# hdmi_trigger_interface.net
KiCad netlist of a schematic drawn in EAGLE
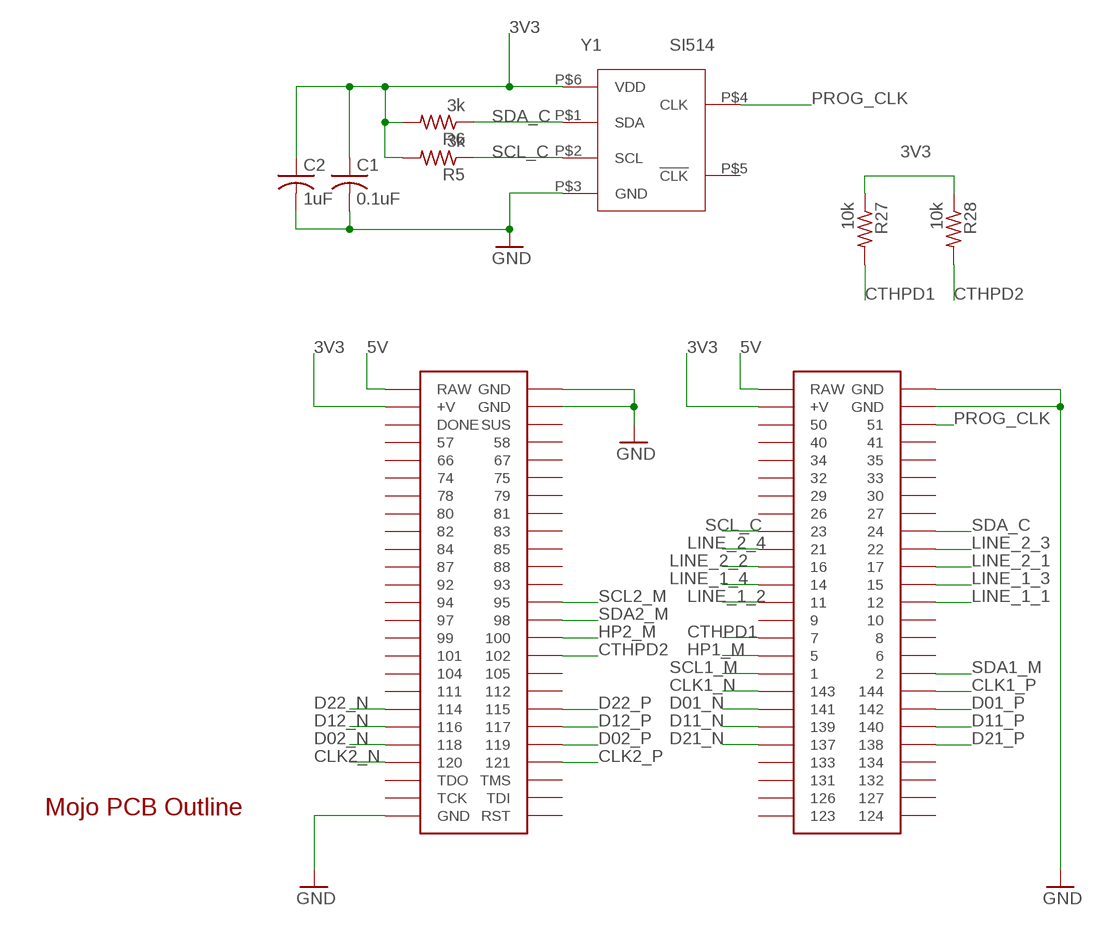
[diagram p0: schematic, sheet 1]
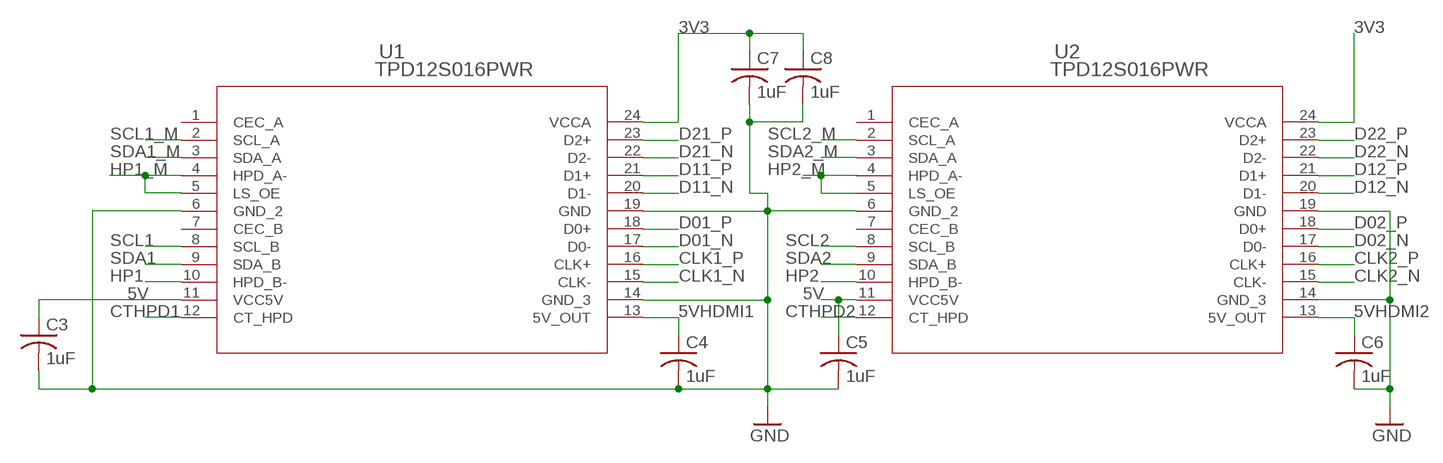
[diagram p1: schematic, sheet 2]
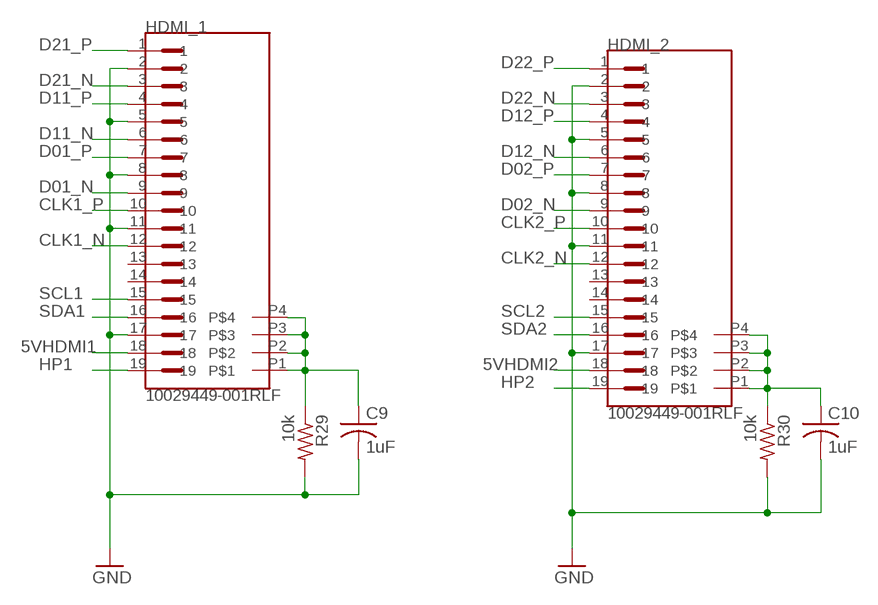
[diagram p2: schematic, sheet 3]
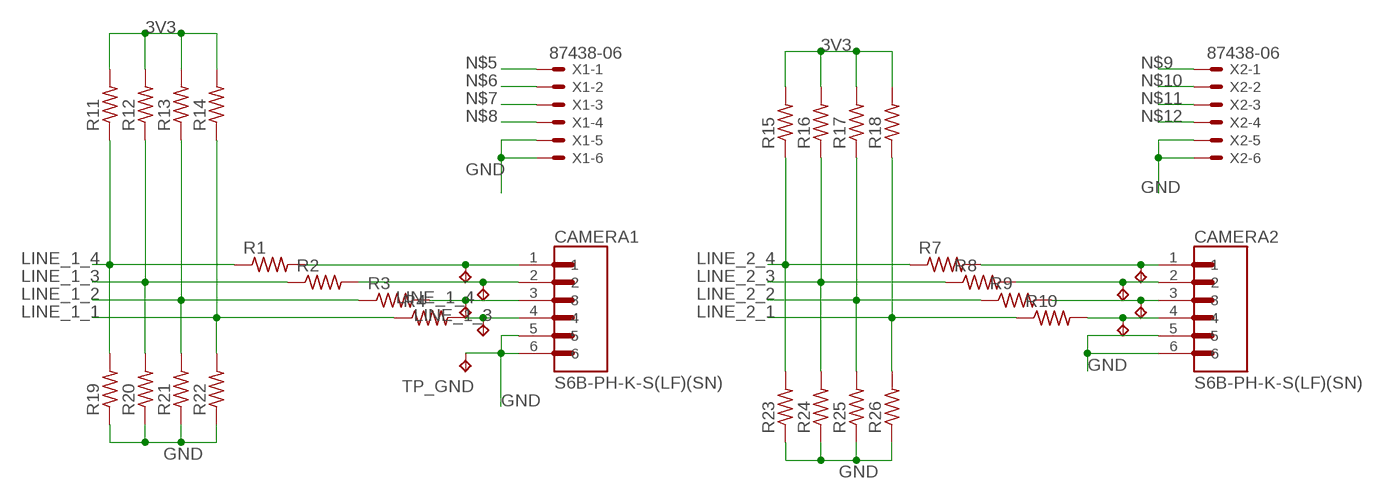
[diagram p3: schematic, sheet 4]

(export (version "E")
  (design (tool "Eeschema 10.0.6"))
  (components
    (comp (ref "C3")
      (value "1uF")
      (footprint "eagle-import:C0603")
      (libsource (lib "eagle-import") (part "C-USC0603"))
    )
    (comp (ref "C4")
      (value "1uF")
      (footprint "eagle-import:C0603")
      (libsource (lib "eagle-import") (part "C-USC0603"))
    )
    (comp (ref "C5")
      (value "1uF")
      (footprint "eagle-import:C0603")
      (libsource (lib "eagle-import") (part "C-USC0603"))
    )
    (comp (ref "C6")
      (value "1uF")
      (footprint "eagle-import:C0603")
      (libsource (lib "eagle-import") (part "C-USC0603"))
    )
    (comp (ref "C7")
      (value "1uF")
      (footprint "eagle-import:C0603")
      (libsource (lib "eagle-import") (part "C-USC0603"))
    )
    (comp (ref "C8")
      (value "1uF")
      (footprint "eagle-import:C0603")
      (libsource (lib "eagle-import") (part "C-USC0603"))
    )
    (comp (ref "U1")
      (value "TPD12S016PWR")
      (footprint "eagle-import:PW24")
      (libsource (lib "eagle-import") (part "TPD12S016PWR"))
    )
    (comp (ref "U2")
      (value "TPD12S016PWR")
      (footprint "eagle-import:PW24")
      (libsource (lib "eagle-import") (part "TPD12S016PWR"))
    )
    (comp (ref "C9")
      (value "1uF")
      (footprint "eagle-import:C0603")
      (libsource (lib "eagle-import") (part "C-USC0603"))
    )
    (comp (ref "C10")
      (value "1uF")
      (footprint "eagle-import:C0603")
      (libsource (lib "eagle-import") (part "C-USC0603"))
    )
    (comp (ref "HDMI_1")
      (value "10029449-001RLF")
      (footprint "eagle-import:FCI_10029449-001RLF")
      (fields (field (name "MF") "Amphenol FCI"))
      (libsource (lib "eagle-import") (part "10029449-001RLF"))
    )
    (comp (ref "HDMI_2")
      (value "10029449-001RLF")
      (footprint "eagle-import:FCI_10029449-001RLF")
      (fields (field (name "MF") "Amphenol FCI"))
      (libsource (lib "eagle-import") (part "10029449-001RLF"))
    )
    (comp (ref "R29")
      (value "10k")
      (footprint "eagle-import:R0603")
      (libsource (lib "eagle-import") (part "R-US_R0603"))
    )
    (comp (ref "R30")
      (value "10k")
      (footprint "eagle-import:R0603")
      (libsource (lib "eagle-import") (part "R-US_R0603"))
    )
    (comp (ref "CAMERA1")
      (value "S6B-PH-K-S(LF)(SN)")
      (footprint "eagle-import:JST_S6B-PH-K-S(LF)(SN)")
      (fields
        (field (name "DIGI-KEY_PART_NUMBER") "455-1723-ND")
        (field (name "MF") "JST Sales")
        (field (name "MP") "S6B-PH-K-S_LF__SN_")
      )
      (libsource (lib "eagle-import") (part "S6B-PH-K-S(LF)(SN)"))
    )
    (comp (ref "CAMERA2")
      (value "S6B-PH-K-S(LF)(SN)")
      (footprint "eagle-import:JST_S6B-PH-K-S(LF)(SN)")
      (fields
        (field (name "DIGI-KEY_PART_NUMBER") "455-1723-ND")
        (field (name "MF") "JST Sales")
        (field (name "MP") "S6B-PH-K-S_LF__SN_")
      )
      (libsource (lib "eagle-import") (part "S6B-PH-K-S(LF)(SN)"))
    )
    (comp (ref "LINE_1_1")
      (value "TPTP16R")
      (footprint "eagle-import:TP16R")
      (libsource (lib "eagle-import") (part "TPTP16R"))
    )
    (comp (ref "LINE_1_2")
      (value "TPTP16R")
      (footprint "eagle-import:TP16R")
      (libsource (lib "eagle-import") (part "TPTP16R"))
    )
    (comp (ref "LINE_1_3")
      (value "TPTP16R")
      (footprint "eagle-import:TP16R")
      (libsource (lib "eagle-import") (part "TPTP16R"))
    )
    (comp (ref "LINE_1_4")
      (value "TPTP16R")
      (footprint "eagle-import:TP16R")
      (libsource (lib "eagle-import") (part "TPTP16R"))
    )
    (comp (ref "LINE_2_1")
      (value "LINE_1")
      (footprint "eagle-import:TP16R")
      (libsource (lib "eagle-import") (part "TPTP16R"))
    )
    (comp (ref "LINE_2_2")
      (value "LINE_2")
      (footprint "eagle-import:TP16R")
      (libsource (lib "eagle-import") (part "TPTP16R"))
    )
    (comp (ref "LINE_2_3")
      (value "LINE_3")
      (footprint "eagle-import:TP16R")
      (libsource (lib "eagle-import") (part "TPTP16R"))
    )
    (comp (ref "LINE_4")
      (value "LINE_1")
      (footprint "eagle-import:TP16R")
      (libsource (lib "eagle-import") (part "TPTP16R"))
    )
    (comp (ref "R1")
      (value "R-US_R0603")
      (footprint "eagle-import:R0603")
      (libsource (lib "eagle-import") (part "R-US_R0603"))
    )
    (comp (ref "R2")
      (value "R-US_R0603")
      (footprint "eagle-import:R0603")
      (libsource (lib "eagle-import") (part "R-US_R0603"))
    )
    (comp (ref "R3")
      (value "R-US_R0603")
      (footprint "eagle-import:R0603")
      (libsource (lib "eagle-import") (part "R-US_R0603"))
    )
    (comp (ref "R4")
      (value "R-US_R0603")
      (footprint "eagle-import:R0603")
      (libsource (lib "eagle-import") (part "R-US_R0603"))
    )
    (comp (ref "R7")
      (value "R-US_R0603")
      (footprint "eagle-import:R0603")
      (libsource (lib "eagle-import") (part "R-US_R0603"))
    )
    (comp (ref "R8")
      (value "R-US_R0603")
      (footprint "eagle-import:R0603")
      (libsource (lib "eagle-import") (part "R-US_R0603"))
    )
    (comp (ref "R9")
      (value "R-US_R0603")
      (footprint "eagle-import:R0603")
      (libsource (lib "eagle-import") (part "R-US_R0603"))
    )
    (comp (ref "R10")
      (value "R-US_R0603")
      (footprint "eagle-import:R0603")
      (libsource (lib "eagle-import") (part "R-US_R0603"))
    )
    (comp (ref "R11")
      (value "R-US_R0603")
      (footprint "eagle-import:R0603")
      (libsource (lib "eagle-import") (part "R-US_R0603"))
    )
    (comp (ref "R12")
      (value "R-US_R0603")
      (footprint "eagle-import:R0603")
      (libsource (lib "eagle-import") (part "R-US_R0603"))
    )
    (comp (ref "R13")
      (value "R-US_R0603")
      (footprint "eagle-import:R0603")
      (libsource (lib "eagle-import") (part "R-US_R0603"))
    )
    (comp (ref "R14")
      (value "R-US_R0603")
      (footprint "eagle-import:R0603")
      (libsource (lib "eagle-import") (part "R-US_R0603"))
    )
    (comp (ref "R15")
      (value "R-US_R0603")
      (footprint "eagle-import:R0603")
      (libsource (lib "eagle-import") (part "R-US_R0603"))
    )
    (comp (ref "R16")
      (value "R-US_R0603")
      (footprint "eagle-import:R0603")
      (libsource (lib "eagle-import") (part "R-US_R0603"))
    )
    (comp (ref "R17")
      (value "R-US_R0603")
      (footprint "eagle-import:R0603")
      (libsource (lib "eagle-import") (part "R-US_R0603"))
    )
    (comp (ref "R18")
      (value "R-US_R0603")
      (footprint "eagle-import:R0603")
      (libsource (lib "eagle-import") (part "R-US_R0603"))
    )
    (comp (ref "R19")
      (value "R-US_R0603")
      (footprint "eagle-import:R0603")
      (libsource (lib "eagle-import") (part "R-US_R0603"))
    )
    (comp (ref "R20")
      (value "R-US_R0603")
      (footprint "eagle-import:R0603")
      (libsource (lib "eagle-import") (part "R-US_R0603"))
    )
    (comp (ref "R21")
      (value "R-US_R0603")
      (footprint "eagle-import:R0603")
      (libsource (lib "eagle-import") (part "R-US_R0603"))
    )
    (comp (ref "R22")
      (value "R-US_R0603")
      (footprint "eagle-import:R0603")
      (libsource (lib "eagle-import") (part "R-US_R0603"))
    )
    (comp (ref "R23")
      (value "R-US_R0603")
      (footprint "eagle-import:R0603")
      (libsource (lib "eagle-import") (part "R-US_R0603"))
    )
    (comp (ref "R24")
      (value "R-US_R0603")
      (footprint "eagle-import:R0603")
      (libsource (lib "eagle-import") (part "R-US_R0603"))
    )
    (comp (ref "R25")
      (value "R-US_R0603")
      (footprint "eagle-import:R0603")
      (libsource (lib "eagle-import") (part "R-US_R0603"))
    )
    (comp (ref "R26")
      (value "R-US_R0603")
      (footprint "eagle-import:R0603")
      (libsource (lib "eagle-import") (part "R-US_R0603"))
    )
    (comp (ref "TP_GND")
      (value "TPTP16R")
      (footprint "eagle-import:TP16R")
      (libsource (lib "eagle-import") (part "TPTP16R"))
    )
    (comp (ref "X1")
      (value "87438-06")
      (footprint "eagle-import:87438-06")
      (fields (field (name "MF") "MOLEX") (field (name "MPN") "87438-0643"))
      (libsource (lib "eagle-import") (part "87438-06"))
    )
    (comp (ref "X2")
      (value "87438-06")
      (footprint "eagle-import:87438-06")
      (fields (field (name "MF") "MOLEX") (field (name "MPN") "87438-0643"))
      (libsource (lib "eagle-import") (part "87438-06"))
    )
    (comp (ref "C1")
      (value "0.1uF")
      (footprint "eagle-import:C0603")
      (libsource (lib "eagle-import") (part "C-USC0603"))
    )
    (comp (ref "C2")
      (value "1uF")
      (footprint "eagle-import:C0603")
      (libsource (lib "eagle-import") (part "C-USC0603"))
    )
    (comp (ref "R5")
      (value "3k")
      (footprint "eagle-import:R0603")
      (libsource (lib "eagle-import") (part "R-US_R0603"))
    )
    (comp (ref "R6")
      (value "3k")
      (footprint "eagle-import:R0603")
      (libsource (lib "eagle-import") (part "R-US_R0603"))
    )
    (comp (ref "R27")
      (value "10k")
      (footprint "eagle-import:R0603")
      (libsource (lib "eagle-import") (part "R-US_R0603"))
    )
    (comp (ref "R28")
      (value "10k")
      (footprint "eagle-import:R0603")
      (libsource (lib "eagle-import") (part "R-US_R0603"))
    )
    (comp (ref "U$1")
      (value "MOJOV3")
      (footprint "eagle-import:MOJO_V3")
      (libsource (lib "eagle-import") (part "MOJOV3"))
    )
    (comp (ref "U$2")
      (value "MOJO_OUTLINE")
      (footprint "eagle-import:MOJO_OUTLINE")
      (libsource (lib "eagle-import") (part "MOJO_OUTLINE"))
    )
    (comp (ref "Y1")
      (value "SI514")
      (footprint "eagle-import:XTAL-6PIN")
      (libsource (lib "eagle-import") (part "SI514"))
    )
  )
  (nets
    (net (code "1") (name "3V3") (class "Default")
      (node (ref "C1") (pin "1") (pinfunction "1_1") (pintype "passive"))
      (node (ref "C2") (pin "1") (pinfunction "1_1") (pintype "passive"))
      (node (ref "C7") (pin "1") (pinfunction "1_1") (pintype "passive"))
      (node (ref "C8") (pin "1") (pinfunction "1_1") (pintype "passive"))
      (node (ref "R11") (pin "2") (pinfunction "2_2") (pintype "passive"))
      (node (ref "R12") (pin "2") (pinfunction "2_2") (pintype "passive"))
      (node (ref "R13") (pin "2") (pinfunction "2_2") (pintype "passive"))
      (node (ref "R14") (pin "2") (pinfunction "2_2") (pintype "passive"))
      (node (ref "R15") (pin "2") (pinfunction "2_2") (pintype "passive"))
      (node (ref "R16") (pin "2") (pinfunction "2_2") (pintype "passive"))
      (node (ref "R17") (pin "2") (pinfunction "2_2") (pintype "passive"))
      (node (ref "R18") (pin "2") (pinfunction "2_2") (pintype "passive"))
      (node (ref "R27") (pin "1") (pinfunction "1_1") (pintype "passive"))
      (node (ref "R28") (pin "1") (pinfunction "1_1") (pintype "passive"))
      (node (ref "R5") (pin "2") (pinfunction "2_2") (pintype "passive"))
      (node (ref "R6") (pin "2") (pinfunction "2_2") (pintype "passive"))
      (node (ref "U$1") (pin "V@1") (pinfunction "+V_V@1") (pintype "power_in"))
      (node (ref "U$1") (pin "V@2") (pinfunction "+V_V@2") (pintype "power_in"))
      (node (ref "U1") (pin "24") (pinfunction "VCCA_24") (pintype "power_in"))
      (node (ref "U2") (pin "24") (pinfunction "VCCA_24") (pintype "power_in"))
      (node (ref "Y1") (pin "P$6") (pinfunction "VDD_P$6") (pintype "bidirectional"))
    )
    (net (code "2") (name "5V") (class "Default")
      (node (ref "C3") (pin "1") (pinfunction "1_1") (pintype "passive"))
      (node (ref "C5") (pin "1") (pinfunction "1_1") (pintype "passive"))
      (node (ref "U$1") (pin "RAW@1") (pinfunction "RAW_RAW@1") (pintype "power_in"))
      (node (ref "U$1") (pin "RAW@2") (pinfunction "RAW_RAW@2") (pintype "power_in"))
      (node (ref "U1") (pin "11") (pinfunction "VCC5V_11") (pintype "power_in"))
      (node (ref "U2") (pin "11") (pinfunction "VCC5V_11") (pintype "power_in"))
    )
    (net (code "3") (name "5VHDMI1") (class "Default")
      (node (ref "C4") (pin "1") (pinfunction "1_1") (pintype "passive"))
      (node (ref "HDMI_1") (pin "18") (pinfunction "18_18") (pintype "passive"))
      (node (ref "U1") (pin "13") (pinfunction "5V_OUT_13") (pintype "output"))
    )
    (net (code "4") (name "5VHDMI2") (class "Default")
      (node (ref "C6") (pin "1") (pinfunction "1_1") (pintype "passive"))
      (node (ref "HDMI_2") (pin "18") (pinfunction "18_18") (pintype "passive"))
      (node (ref "U2") (pin "13") (pinfunction "5V_OUT_13") (pintype "output"))
    )
    (net (code "5") (name "CLK1_N") (class "Default")
      (node (ref "HDMI_1") (pin "12") (pinfunction "12_12") (pintype "passive"))
      (node (ref "U$1") (pin "143") (pinfunction "143_143") (pintype "bidirectional"))
      (node (ref "U1") (pin "15") (pinfunction "CLK-_15") (pintype "passive"))
    )
    (net (code "6") (name "CLK1_P") (class "Default")
      (node (ref "HDMI_1") (pin "10") (pinfunction "10_10") (pintype "passive"))
      (node (ref "U$1") (pin "144") (pinfunction "144_144") (pintype "bidirectional"))
      (node (ref "U1") (pin "16") (pinfunction "CLK+_16") (pintype "passive"))
    )
    (net (code "7") (name "CLK2_N") (class "Default")
      (node (ref "HDMI_2") (pin "12") (pinfunction "12_12") (pintype "passive"))
      (node (ref "U$1") (pin "120") (pinfunction "120_120") (pintype "bidirectional"))
      (node (ref "U2") (pin "15") (pinfunction "CLK-_15") (pintype "passive"))
    )
    (net (code "8") (name "CLK2_P") (class "Default")
      (node (ref "HDMI_2") (pin "10") (pinfunction "10_10") (pintype "passive"))
      (node (ref "U$1") (pin "121") (pinfunction "121_121") (pintype "bidirectional"))
      (node (ref "U2") (pin "16") (pinfunction "CLK+_16") (pintype "passive"))
    )
    (net (code "9") (name "CTHPD1") (class "Default")
      (node (ref "R27") (pin "2") (pinfunction "2_2") (pintype "passive"))
      (node (ref "U$1") (pin "7") (pinfunction "7_7") (pintype "bidirectional"))
      (node (ref "U1") (pin "12") (pinfunction "CT_HPD_12") (pintype "input"))
    )
    (net (code "10") (name "CTHPD2") (class "Default")
      (node (ref "R28") (pin "2") (pinfunction "2_2") (pintype "passive"))
      (node (ref "U$1") (pin "102") (pinfunction "102_102") (pintype "bidirectional"))
      (node (ref "U2") (pin "12") (pinfunction "CT_HPD_12") (pintype "input"))
    )
    (net (code "11") (name "D01_N") (class "Default")
      (node (ref "HDMI_1") (pin "9") (pinfunction "9_9") (pintype "passive"))
      (node (ref "U$1") (pin "141") (pinfunction "141_141") (pintype "bidirectional"))
      (node (ref "U1") (pin "17") (pinfunction "D0-_17") (pintype "passive"))
    )
    (net (code "12") (name "D01_P") (class "Default")
      (node (ref "HDMI_1") (pin "7") (pinfunction "7_7") (pintype "passive"))
      (node (ref "U$1") (pin "142") (pinfunction "142_142") (pintype "bidirectional"))
      (node (ref "U1") (pin "18") (pinfunction "D0+_18") (pintype "passive"))
    )
    (net (code "13") (name "D02_N") (class "Default")
      (node (ref "HDMI_2") (pin "9") (pinfunction "9_9") (pintype "passive"))
      (node (ref "U$1") (pin "118") (pinfunction "118_118") (pintype "bidirectional"))
      (node (ref "U2") (pin "17") (pinfunction "D0-_17") (pintype "passive"))
    )
    (net (code "14") (name "D02_P") (class "Default")
      (node (ref "HDMI_2") (pin "7") (pinfunction "7_7") (pintype "passive"))
      (node (ref "U$1") (pin "119") (pinfunction "119_119") (pintype "bidirectional"))
      (node (ref "U2") (pin "18") (pinfunction "D0+_18") (pintype "passive"))
    )
    (net (code "15") (name "D11_N") (class "Default")
      (node (ref "HDMI_1") (pin "6") (pinfunction "6_6") (pintype "passive"))
      (node (ref "U$1") (pin "139") (pinfunction "139_139") (pintype "bidirectional"))
      (node (ref "U1") (pin "20") (pinfunction "D1-_20") (pintype "passive"))
    )
    (net (code "16") (name "D11_P") (class "Default")
      (node (ref "HDMI_1") (pin "4") (pinfunction "4_4") (pintype "passive"))
      (node (ref "U$1") (pin "140") (pinfunction "140_140") (pintype "bidirectional"))
      (node (ref "U1") (pin "21") (pinfunction "D1+_21") (pintype "passive"))
    )
    (net (code "17") (name "D12_N") (class "Default")
      (node (ref "HDMI_2") (pin "6") (pinfunction "6_6") (pintype "passive"))
      (node (ref "U$1") (pin "116") (pinfunction "116_116") (pintype "bidirectional"))
      (node (ref "U2") (pin "20") (pinfunction "D1-_20") (pintype "passive"))
    )
    (net (code "18") (name "D12_P") (class "Default")
      (node (ref "HDMI_2") (pin "4") (pinfunction "4_4") (pintype "passive"))
      (node (ref "U$1") (pin "117") (pinfunction "117_117") (pintype "bidirectional"))
      (node (ref "U2") (pin "21") (pinfunction "D1+_21") (pintype "passive"))
    )
    (net (code "19") (name "D21_N") (class "Default")
      (node (ref "HDMI_1") (pin "3") (pinfunction "3_3") (pintype "passive"))
      (node (ref "U$1") (pin "137") (pinfunction "137_137") (pintype "bidirectional"))
      (node (ref "U1") (pin "22") (pinfunction "D2-_22") (pintype "passive"))
    )
    (net (code "20") (name "D21_P") (class "Default")
      (node (ref "HDMI_1") (pin "1") (pinfunction "1_1") (pintype "passive"))
      (node (ref "U$1") (pin "138") (pinfunction "138_138") (pintype "bidirectional"))
      (node (ref "U1") (pin "23") (pinfunction "D2+_23") (pintype "passive"))
    )
    (net (code "21") (name "D22_N") (class "Default")
      (node (ref "HDMI_2") (pin "3") (pinfunction "3_3") (pintype "passive"))
      (node (ref "U$1") (pin "114") (pinfunction "114_114") (pintype "bidirectional"))
      (node (ref "U2") (pin "22") (pinfunction "D2-_22") (pintype "passive"))
    )
    (net (code "22") (name "D22_P") (class "Default")
      (node (ref "HDMI_2") (pin "1") (pinfunction "1_1") (pintype "passive"))
      (node (ref "U$1") (pin "115") (pinfunction "115_115") (pintype "bidirectional"))
      (node (ref "U2") (pin "23") (pinfunction "D2+_23") (pintype "passive"))
    )
    (net (code "23") (name "GND") (class "Default")
      (node (ref "C1") (pin "2") (pinfunction "2_2") (pintype "passive"))
      (node (ref "C10") (pin "2") (pinfunction "2_2") (pintype "passive"))
      (node (ref "C2") (pin "2") (pinfunction "2_2") (pintype "passive"))
      (node (ref "C3") (pin "2") (pinfunction "2_2") (pintype "passive"))
      (node (ref "C4") (pin "2") (pinfunction "2_2") (pintype "passive"))
      (node (ref "C5") (pin "2") (pinfunction "2_2") (pintype "passive"))
      (node (ref "C6") (pin "2") (pinfunction "2_2") (pintype "passive"))
      (node (ref "C7") (pin "2") (pinfunction "2_2") (pintype "passive"))
      (node (ref "C8") (pin "2") (pinfunction "2_2") (pintype "passive"))
      (node (ref "C9") (pin "2") (pinfunction "2_2") (pintype "passive"))
      (node (ref "CAMERA1") (pin "5") (pinfunction "5_5") (pintype "passive"))
      (node (ref "CAMERA1") (pin "6") (pinfunction "6_6") (pintype "passive"))
      (node (ref "CAMERA2") (pin "5") (pinfunction "5_5") (pintype "passive"))
      (node (ref "CAMERA2") (pin "6") (pinfunction "6_6") (pintype "passive"))
      (node (ref "HDMI_1") (pin "11") (pinfunction "11_11") (pintype "passive"))
      (node (ref "HDMI_1") (pin "17") (pinfunction "17_17") (pintype "passive"))
      (node (ref "HDMI_1") (pin "2") (pinfunction "2_2") (pintype "passive"))
      (node (ref "HDMI_1") (pin "5") (pinfunction "5_5") (pintype "passive"))
      (node (ref "HDMI_1") (pin "8") (pinfunction "8_8") (pintype "passive"))
      (node (ref "HDMI_2") (pin "11") (pinfunction "11_11") (pintype "passive"))
      (node (ref "HDMI_2") (pin "17") (pinfunction "17_17") (pintype "passive"))
      (node (ref "HDMI_2") (pin "2") (pinfunction "2_2") (pintype "passive"))
      (node (ref "HDMI_2") (pin "5") (pinfunction "5_5") (pintype "passive"))
      (node (ref "HDMI_2") (pin "8") (pinfunction "8_8") (pintype "passive"))
      (node (ref "R19") (pin "1") (pinfunction "1_1") (pintype "passive"))
      (node (ref "R20") (pin "1") (pinfunction "1_1") (pintype "passive"))
      (node (ref "R21") (pin "1") (pinfunction "1_1") (pintype "passive"))
      (node (ref "R22") (pin "1") (pinfunction "1_1") (pintype "passive"))
      (node (ref "R23") (pin "1") (pinfunction "1_1") (pintype "passive"))
      (node (ref "R24") (pin "1") (pinfunction "1_1") (pintype "passive"))
      (node (ref "R25") (pin "1") (pinfunction "1_1") (pintype "passive"))
      (node (ref "R26") (pin "1") (pinfunction "1_1") (pintype "passive"))
      (node (ref "R29") (pin "2") (pinfunction "2_2") (pintype "passive"))
      (node (ref "R30") (pin "2") (pinfunction "2_2") (pintype "passive"))
      (node (ref "TP_GND") (pin "TP") (pinfunction "TP_TP") (pintype "input"))
      (node (ref "U$1") (pin "GND@1") (pinfunction "GND_GND@1") (pintype "power_in"))
      (node (ref "U$1") (pin "GND@2") (pinfunction "GND_GND@2") (pintype "power_in"))
      (node (ref "U$1") (pin "GND@3") (pinfunction "GND_GND@3") (pintype "power_in"))
      (node (ref "U$1") (pin "GND@4") (pinfunction "GND_GND@4") (pintype "power_in"))
      (node (ref "U$1") (pin "GND@6") (pinfunction "GND_GND@6") (pintype "power_in"))
      (node (ref "U1") (pin "14") (pinfunction "GND_3_14") (pintype "power_in"))
      (node (ref "U1") (pin "19") (pinfunction "GND_19") (pintype "power_in"))
      (node (ref "U1") (pin "6") (pinfunction "GND_2_6") (pintype "power_in"))
      (node (ref "U2") (pin "14") (pinfunction "GND_3_14") (pintype "power_in"))
      (node (ref "U2") (pin "19") (pinfunction "GND_19") (pintype "power_in"))
      (node (ref "U2") (pin "6") (pinfunction "GND_2_6") (pintype "power_in"))
      (node (ref "X1") (pin "5") (pinfunction "S_5") (pintype "passive"))
      (node (ref "X1") (pin "6") (pinfunction "S_6") (pintype "passive"))
      (node (ref "X2") (pin "5") (pinfunction "S_5") (pintype "passive"))
      (node (ref "X2") (pin "6") (pinfunction "S_6") (pintype "passive"))
      (node (ref "Y1") (pin "P$3") (pinfunction "GND_P$3") (pintype "bidirectional"))
    )
    (net (code "24") (name "HP1") (class "Default")
      (node (ref "HDMI_1") (pin "19") (pinfunction "19_19") (pintype "passive"))
      (node (ref "U1") (pin "10") (pinfunction "HPD_B-_10") (pintype "input"))
    )
    (net (code "25") (name "HP1_M") (class "Default")
      (node (ref "U$1") (pin "5") (pinfunction "5_5") (pintype "bidirectional"))
      (node (ref "U1") (pin "4") (pinfunction "HPD_A-_4") (pintype "output"))
      (node (ref "U1") (pin "5") (pinfunction "LS_OE_5") (pintype "input"))
    )
    (net (code "26") (name "HP2") (class "Default")
      (node (ref "HDMI_2") (pin "19") (pinfunction "19_19") (pintype "passive"))
      (node (ref "U2") (pin "10") (pinfunction "HPD_B-_10") (pintype "input"))
    )
    (net (code "27") (name "HP2_M") (class "Default")
      (node (ref "U$1") (pin "100") (pinfunction "100_100") (pintype "bidirectional"))
      (node (ref "U2") (pin "4") (pinfunction "HPD_A-_4") (pintype "output"))
      (node (ref "U2") (pin "5") (pinfunction "LS_OE_5") (pintype "input"))
    )
    (net (code "28") (name "LINE_1_1") (class "Default")
      (node (ref "R14") (pin "1") (pinfunction "1_1") (pintype "passive"))
      (node (ref "R22") (pin "2") (pinfunction "2_2") (pintype "passive"))
      (node (ref "R4") (pin "1") (pinfunction "1_1") (pintype "passive"))
      (node (ref "U$1") (pin "12") (pinfunction "12_12") (pintype "bidirectional"))
    )
    (net (code "29") (name "LINE_1_2") (class "Default")
      (node (ref "R13") (pin "1") (pinfunction "1_1") (pintype "passive"))
      (node (ref "R21") (pin "2") (pinfunction "2_2") (pintype "passive"))
      (node (ref "R3") (pin "1") (pinfunction "1_1") (pintype "passive"))
      (node (ref "U$1") (pin "11") (pinfunction "11_11") (pintype "bidirectional"))
    )
    (net (code "30") (name "LINE_1_3") (class "Default")
      (node (ref "R12") (pin "1") (pinfunction "1_1") (pintype "passive"))
      (node (ref "R2") (pin "1") (pinfunction "1_1") (pintype "passive"))
      (node (ref "R20") (pin "2") (pinfunction "2_2") (pintype "passive"))
      (node (ref "U$1") (pin "15") (pinfunction "15_15") (pintype "bidirectional"))
    )
    (net (code "31") (name "LINE_1_4") (class "Default")
      (node (ref "R1") (pin "1") (pinfunction "1_1") (pintype "passive"))
      (node (ref "R11") (pin "1") (pinfunction "1_1") (pintype "passive"))
      (node (ref "R19") (pin "2") (pinfunction "2_2") (pintype "passive"))
      (node (ref "U$1") (pin "14") (pinfunction "14_14") (pintype "bidirectional"))
    )
    (net (code "32") (name "LINE_2_1") (class "Default")
      (node (ref "R10") (pin "1") (pinfunction "1_1") (pintype "passive"))
      (node (ref "R18") (pin "1") (pinfunction "1_1") (pintype "passive"))
      (node (ref "R26") (pin "2") (pinfunction "2_2") (pintype "passive"))
      (node (ref "U$1") (pin "17") (pinfunction "17_17") (pintype "bidirectional"))
    )
    (net (code "33") (name "LINE_2_2") (class "Default")
      (node (ref "R17") (pin "1") (pinfunction "1_1") (pintype "passive"))
      (node (ref "R25") (pin "2") (pinfunction "2_2") (pintype "passive"))
      (node (ref "R9") (pin "1") (pinfunction "1_1") (pintype "passive"))
      (node (ref "U$1") (pin "16") (pinfunction "16_16") (pintype "bidirectional"))
    )
    (net (code "34") (name "LINE_2_3") (class "Default")
      (node (ref "R16") (pin "1") (pinfunction "1_1") (pintype "passive"))
      (node (ref "R24") (pin "2") (pinfunction "2_2") (pintype "passive"))
      (node (ref "R8") (pin "1") (pinfunction "1_1") (pintype "passive"))
      (node (ref "U$1") (pin "22") (pinfunction "22_22") (pintype "bidirectional"))
    )
    (net (code "35") (name "LINE_2_4") (class "Default")
      (node (ref "R15") (pin "1") (pinfunction "1_1") (pintype "passive"))
      (node (ref "R23") (pin "2") (pinfunction "2_2") (pintype "passive"))
      (node (ref "R7") (pin "1") (pinfunction "1_1") (pintype "passive"))
      (node (ref "U$1") (pin "21") (pinfunction "21_21") (pintype "bidirectional"))
    )
    (net (code "36") (name "N$5") (class "Default")
      (node (ref "CAMERA1") (pin "1") (pinfunction "1_1") (pintype "passive"))
      (node (ref "LINE_1_4") (pin "TP") (pinfunction "TP_TP") (pintype "input"))
      (node (ref "R1") (pin "2") (pinfunction "2_2") (pintype "passive"))
      (node (ref "X1") (pin "1") (pinfunction "S_1") (pintype "passive"))
    )
    (net (code "37") (name "N$6") (class "Default")
      (node (ref "CAMERA1") (pin "2") (pinfunction "2_2") (pintype "passive"))
      (node (ref "LINE_1_3") (pin "TP") (pinfunction "TP_TP") (pintype "input"))
      (node (ref "R2") (pin "2") (pinfunction "2_2") (pintype "passive"))
      (node (ref "X1") (pin "2") (pinfunction "S_2") (pintype "passive"))
    )
    (net (code "38") (name "N$7") (class "Default")
      (node (ref "CAMERA1") (pin "3") (pinfunction "3_3") (pintype "passive"))
      (node (ref "LINE_1_2") (pin "TP") (pinfunction "TP_TP") (pintype "input"))
      (node (ref "R3") (pin "2") (pinfunction "2_2") (pintype "passive"))
      (node (ref "X1") (pin "3") (pinfunction "S_3") (pintype "passive"))
    )
    (net (code "39") (name "N$8") (class "Default")
      (node (ref "CAMERA1") (pin "4") (pinfunction "4_4") (pintype "passive"))
      (node (ref "LINE_1_1") (pin "TP") (pinfunction "TP_TP") (pintype "input"))
      (node (ref "R4") (pin "2") (pinfunction "2_2") (pintype "passive"))
      (node (ref "X1") (pin "4") (pinfunction "S_4") (pintype "passive"))
    )
    (net (code "40") (name "N$9") (class "Default")
      (node (ref "CAMERA2") (pin "1") (pinfunction "1_1") (pintype "passive"))
      (node (ref "LINE_4") (pin "TP") (pinfunction "TP_TP") (pintype "input"))
      (node (ref "R7") (pin "2") (pinfunction "2_2") (pintype "passive"))
      (node (ref "X2") (pin "1") (pinfunction "S_1") (pintype "passive"))
    )
    (net (code "41") (name "N$10") (class "Default")
      (node (ref "CAMERA2") (pin "2") (pinfunction "2_2") (pintype "passive"))
      (node (ref "LINE_2_3") (pin "TP") (pinfunction "TP_TP") (pintype "input"))
      (node (ref "R8") (pin "2") (pinfunction "2_2") (pintype "passive"))
      (node (ref "X2") (pin "2") (pinfunction "S_2") (pintype "passive"))
    )
    (net (code "42") (name "N$11") (class "Default")
      (node (ref "CAMERA2") (pin "3") (pinfunction "3_3") (pintype "passive"))
      (node (ref "LINE_2_2") (pin "TP") (pinfunction "TP_TP") (pintype "input"))
      (node (ref "R9") (pin "2") (pinfunction "2_2") (pintype "passive"))
      (node (ref "X2") (pin "3") (pinfunction "S_3") (pintype "passive"))
    )
    (net (code "43") (name "N$12") (class "Default")
      (node (ref "CAMERA2") (pin "4") (pinfunction "4_4") (pintype "passive"))
      (node (ref "LINE_2_1") (pin "TP") (pinfunction "TP_TP") (pintype "input"))
      (node (ref "R10") (pin "2") (pinfunction "2_2") (pintype "passive"))
      (node (ref "X2") (pin "4") (pinfunction "S_4") (pintype "passive"))
    )
    (net (code "44") (name "Net-(HDMI_1-P$1)") (class "Default")
      (node (ref "C9") (pin "1") (pinfunction "1_1") (pintype "passive"))
      (node (ref "HDMI_1") (pin "P1") (pinfunction "P$1_P1") (pintype "bidirectional"))
      (node (ref "HDMI_1") (pin "P2") (pinfunction "P$2_P2") (pintype "bidirectional"))
      (node (ref "HDMI_1") (pin "P3") (pinfunction "P$3_P3") (pintype "bidirectional"))
      (node (ref "HDMI_1") (pin "P4") (pinfunction "P$4_P4") (pintype "bidirectional"))
      (node (ref "R29") (pin "1") (pinfunction "1_1") (pintype "passive"))
    )
    (net (code "45") (name "Net-(HDMI_2-P$1)") (class "Default")
      (node (ref "C10") (pin "1") (pinfunction "1_1") (pintype "passive"))
      (node (ref "HDMI_2") (pin "P1") (pinfunction "P$1_P1") (pintype "bidirectional"))
      (node (ref "HDMI_2") (pin "P2") (pinfunction "P$2_P2") (pintype "bidirectional"))
      (node (ref "HDMI_2") (pin "P3") (pinfunction "P$3_P3") (pintype "bidirectional"))
      (node (ref "HDMI_2") (pin "P4") (pinfunction "P$4_P4") (pintype "bidirectional"))
      (node (ref "R30") (pin "1") (pinfunction "1_1") (pintype "passive"))
    )
    (net (code "46") (name "PROG_CLK") (class "Default")
      (node (ref "U$1") (pin "51") (pinfunction "51_51") (pintype "bidirectional"))
      (node (ref "Y1") (pin "P$4") (pinfunction "CLK_P$4") (pintype "bidirectional"))
    )
    (net (code "47") (name "SCL1") (class "Default")
      (node (ref "HDMI_1") (pin "15") (pinfunction "15_15") (pintype "passive"))
      (node (ref "U1") (pin "8") (pinfunction "SCL_B_8") (pintype "bidirectional"))
    )
    (net (code "48") (name "SCL1_M") (class "Default")
      (node (ref "U$1") (pin "1") (pinfunction "1_1") (pintype "bidirectional"))
      (node (ref "U1") (pin "2") (pinfunction "SCL_A_2") (pintype "bidirectional"))
    )
    (net (code "49") (name "SCL2") (class "Default")
      (node (ref "HDMI_2") (pin "15") (pinfunction "15_15") (pintype "passive"))
      (node (ref "U2") (pin "8") (pinfunction "SCL_B_8") (pintype "bidirectional"))
    )
    (net (code "50") (name "SCL2_M") (class "Default")
      (node (ref "U$1") (pin "95") (pinfunction "95_95") (pintype "bidirectional"))
      (node (ref "U2") (pin "2") (pinfunction "SCL_A_2") (pintype "bidirectional"))
    )
    (net (code "51") (name "SCL_C") (class "Default")
      (node (ref "R5") (pin "1") (pinfunction "1_1") (pintype "passive"))
      (node (ref "U$1") (pin "23") (pinfunction "23_23") (pintype "bidirectional"))
      (node (ref "Y1") (pin "P$2") (pinfunction "SCL_P$2") (pintype "bidirectional"))
    )
    (net (code "52") (name "SDA1") (class "Default")
      (node (ref "HDMI_1") (pin "16") (pinfunction "16_16") (pintype "passive"))
      (node (ref "U1") (pin "9") (pinfunction "SDA_B_9") (pintype "bidirectional"))
    )
    (net (code "53") (name "SDA1_M") (class "Default")
      (node (ref "U$1") (pin "2") (pinfunction "2_2") (pintype "bidirectional"))
      (node (ref "U1") (pin "3") (pinfunction "SDA_A_3") (pintype "bidirectional"))
    )
    (net (code "54") (name "SDA2") (class "Default")
      (node (ref "HDMI_2") (pin "16") (pinfunction "16_16") (pintype "passive"))
      (node (ref "U2") (pin "9") (pinfunction "SDA_B_9") (pintype "bidirectional"))
    )
    (net (code "55") (name "SDA2_M") (class "Default")
      (node (ref "U$1") (pin "98") (pinfunction "98_98") (pintype "bidirectional"))
      (node (ref "U2") (pin "3") (pinfunction "SDA_A_3") (pintype "bidirectional"))
    )
    (net (code "56") (name "SDA_C") (class "Default")
      (node (ref "R6") (pin "1") (pinfunction "1_1") (pintype "passive"))
      (node (ref "U$1") (pin "24") (pinfunction "24_24") (pintype "bidirectional"))
      (node (ref "Y1") (pin "P$1") (pinfunction "SDA_P$1") (pintype "bidirectional"))
    )
    (net (code "57") (name "unconnected-(HDMI_1-Pad13)") (class "Default")
      (node (ref "HDMI_1") (pin "13") (pinfunction "13_13") (pintype "passive"))
    )
    (net (code "58") (name "unconnected-(HDMI_1-Pad14)") (class "Default")
      (node (ref "HDMI_1") (pin "14") (pinfunction "14_14") (pintype "passive"))
    )
    (net (code "59") (name "unconnected-(HDMI_2-Pad13)") (class "Default")
      (node (ref "HDMI_2") (pin "13") (pinfunction "13_13") (pintype "passive"))
    )
    (net (code "60") (name "unconnected-(HDMI_2-Pad14)") (class "Default")
      (node (ref "HDMI_2") (pin "14") (pinfunction "14_14") (pintype "passive"))
    )
    (net (code "61") (name "unconnected-(U$1-Pad6)") (class "Default")
      (node (ref "U$1") (pin "6") (pinfunction "6_6") (pintype "bidirectional"))
    )
    (net (code "62") (name "unconnected-(U$1-Pad8)") (class "Default")
      (node (ref "U$1") (pin "8") (pinfunction "8_8") (pintype "bidirectional"))
    )
    (net (code "63") (name "unconnected-(U$1-Pad9)") (class "Default")
      (node (ref "U$1") (pin "9") (pinfunction "9_9") (pintype "bidirectional"))
    )
    (net (code "64") (name "unconnected-(U$1-Pad10)") (class "Default")
      (node (ref "U$1") (pin "10") (pinfunction "10_10") (pintype "bidirectional"))
    )
    (net (code "65") (name "unconnected-(U$1-Pad26)") (class "Default")
      (node (ref "U$1") (pin "26") (pinfunction "26_26") (pintype "bidirectional"))
    )
    (net (code "66") (name "unconnected-(U$1-Pad27)") (class "Default")
      (node (ref "U$1") (pin "27") (pinfunction "27_27") (pintype "bidirectional"))
    )
    (net (code "67") (name "unconnected-(U$1-Pad29)") (class "Default")
      (node (ref "U$1") (pin "29") (pinfunction "29_29") (pintype "bidirectional"))
    )
    (net (code "68") (name "unconnected-(U$1-Pad30)") (class "Default")
      (node (ref "U$1") (pin "30") (pinfunction "30_30") (pintype "bidirectional"))
    )
    (net (code "69") (name "unconnected-(U$1-Pad32)") (class "Default")
      (node (ref "U$1") (pin "32") (pinfunction "32_32") (pintype "bidirectional"))
    )
    (net (code "70") (name "unconnected-(U$1-Pad33)") (class "Default")
      (node (ref "U$1") (pin "33") (pinfunction "33_33") (pintype "bidirectional"))
    )
    (net (code "71") (name "unconnected-(U$1-Pad34)") (class "Default")
      (node (ref "U$1") (pin "34") (pinfunction "34_34") (pintype "bidirectional"))
    )
    (net (code "72") (name "unconnected-(U$1-Pad35)") (class "Default")
      (node (ref "U$1") (pin "35") (pinfunction "35_35") (pintype "bidirectional"))
    )
    (net (code "73") (name "unconnected-(U$1-Pad40)") (class "Default")
      (node (ref "U$1") (pin "40") (pinfunction "40_40") (pintype "bidirectional"))
    )
    (net (code "74") (name "unconnected-(U$1-Pad41)") (class "Default")
      (node (ref "U$1") (pin "41") (pinfunction "41_41") (pintype "bidirectional"))
    )
    (net (code "75") (name "unconnected-(U$1-Pad50)") (class "Default")
      (node (ref "U$1") (pin "50") (pinfunction "50_50") (pintype "bidirectional"))
    )
    (net (code "76") (name "unconnected-(U$1-Pad57)") (class "Default")
      (node (ref "U$1") (pin "57") (pinfunction "57_57") (pintype "bidirectional"))
    )
    (net (code "77") (name "unconnected-(U$1-Pad58)") (class "Default")
      (node (ref "U$1") (pin "58") (pinfunction "58_58") (pintype "bidirectional"))
    )
    (net (code "78") (name "unconnected-(U$1-Pad66)") (class "Default")
      (node (ref "U$1") (pin "66") (pinfunction "66_66") (pintype "bidirectional"))
    )
    (net (code "79") (name "unconnected-(U$1-Pad67)") (class "Default")
      (node (ref "U$1") (pin "67") (pinfunction "67_67") (pintype "bidirectional"))
    )
    (net (code "80") (name "unconnected-(U$1-Pad74)") (class "Default")
      (node (ref "U$1") (pin "74") (pinfunction "74_74") (pintype "bidirectional"))
    )
    (net (code "81") (name "unconnected-(U$1-Pad75)") (class "Default")
      (node (ref "U$1") (pin "75") (pinfunction "75_75") (pintype "bidirectional"))
    )
    (net (code "82") (name "unconnected-(U$1-Pad78)") (class "Default")
      (node (ref "U$1") (pin "78") (pinfunction "78_78") (pintype "bidirectional"))
    )
    (net (code "83") (name "unconnected-(U$1-Pad79)") (class "Default")
      (node (ref "U$1") (pin "79") (pinfunction "79_79") (pintype "bidirectional"))
    )
    (net (code "84") (name "unconnected-(U$1-Pad80)") (class "Default")
      (node (ref "U$1") (pin "80") (pinfunction "80_80") (pintype "bidirectional"))
    )
    (net (code "85") (name "unconnected-(U$1-Pad81)") (class "Default")
      (node (ref "U$1") (pin "81") (pinfunction "81_81") (pintype "bidirectional"))
    )
    (net (code "86") (name "unconnected-(U$1-Pad82)") (class "Default")
      (node (ref "U$1") (pin "82") (pinfunction "82_82") (pintype "bidirectional"))
    )
    (net (code "87") (name "unconnected-(U$1-Pad83)") (class "Default")
      (node (ref "U$1") (pin "83") (pinfunction "83_83") (pintype "bidirectional"))
    )
    (net (code "88") (name "unconnected-(U$1-Pad84)") (class "Default")
      (node (ref "U$1") (pin "84") (pinfunction "84_84") (pintype "bidirectional"))
    )
    (net (code "89") (name "unconnected-(U$1-Pad85)") (class "Default")
      (node (ref "U$1") (pin "85") (pinfunction "85_85") (pintype "bidirectional"))
    )
    (net (code "90") (name "unconnected-(U$1-Pad87)") (class "Default")
      (node (ref "U$1") (pin "87") (pinfunction "87_87") (pintype "bidirectional"))
    )
    (net (code "91") (name "unconnected-(U$1-Pad88)") (class "Default")
      (node (ref "U$1") (pin "88") (pinfunction "88_88") (pintype "bidirectional"))
    )
    (net (code "92") (name "unconnected-(U$1-Pad92)") (class "Default")
      (node (ref "U$1") (pin "92") (pinfunction "92_92") (pintype "bidirectional"))
    )
    (net (code "93") (name "unconnected-(U$1-Pad93)") (class "Default")
      (node (ref "U$1") (pin "93") (pinfunction "93_93") (pintype "bidirectional"))
    )
    (net (code "94") (name "unconnected-(U$1-Pad94)") (class "Default")
      (node (ref "U$1") (pin "94") (pinfunction "94_94") (pintype "bidirectional"))
    )
    (net (code "95") (name "unconnected-(U$1-Pad97)") (class "Default")
      (node (ref "U$1") (pin "97") (pinfunction "97_97") (pintype "bidirectional"))
    )
    (net (code "96") (name "unconnected-(U$1-Pad99)") (class "Default")
      (node (ref "U$1") (pin "99") (pinfunction "99_99") (pintype "bidirectional"))
    )
    (net (code "97") (name "unconnected-(U$1-Pad101)") (class "Default")
      (node (ref "U$1") (pin "101") (pinfunction "101_101") (pintype "bidirectional"))
    )
    (net (code "98") (name "unconnected-(U$1-Pad104)") (class "Default")
      (node (ref "U$1") (pin "104") (pinfunction "104_104") (pintype "bidirectional"))
    )
    (net (code "99") (name "unconnected-(U$1-Pad105)") (class "Default")
      (node (ref "U$1") (pin "105") (pinfunction "105_105") (pintype "bidirectional"))
    )
    (net (code "100") (name "unconnected-(U$1-Pad111)") (class "Default")
      (node (ref "U$1") (pin "111") (pinfunction "111_111") (pintype "bidirectional"))
    )
    (net (code "101") (name "unconnected-(U$1-Pad112)") (class "Default")
      (node (ref "U$1") (pin "112") (pinfunction "112_112") (pintype "bidirectional"))
    )
    (net (code "102") (name "unconnected-(U$1-Pad123)") (class "Default")
      (node (ref "U$1") (pin "123") (pinfunction "123_123") (pintype "bidirectional"))
    )
    (net (code "103") (name "unconnected-(U$1-Pad124)") (class "Default")
      (node (ref "U$1") (pin "124") (pinfunction "124_124") (pintype "bidirectional"))
    )
    (net (code "104") (name "unconnected-(U$1-Pad126)") (class "Default")
      (node (ref "U$1") (pin "126") (pinfunction "126_126") (pintype "bidirectional"))
    )
    (net (code "105") (name "unconnected-(U$1-Pad127)") (class "Default")
      (node (ref "U$1") (pin "127") (pinfunction "127_127") (pintype "bidirectional"))
    )
    (net (code "106") (name "unconnected-(U$1-Pad131)") (class "Default")
      (node (ref "U$1") (pin "131") (pinfunction "131_131") (pintype "bidirectional"))
    )
    (net (code "107") (name "unconnected-(U$1-Pad132)") (class "Default")
      (node (ref "U$1") (pin "132") (pinfunction "132_132") (pintype "bidirectional"))
    )
    (net (code "108") (name "unconnected-(U$1-Pad133)") (class "Default")
      (node (ref "U$1") (pin "133") (pinfunction "133_133") (pintype "bidirectional"))
    )
    (net (code "109") (name "unconnected-(U$1-Pad134)") (class "Default")
      (node (ref "U$1") (pin "134") (pinfunction "134_134") (pintype "bidirectional"))
    )
    (net (code "110") (name "unconnected-(U$1-PadDONE)") (class "Default")
      (node (ref "U$1") (pin "DONE") (pinfunction "DONE_DONE") (pintype "bidirectional"))
    )
    (net (code "111") (name "unconnected-(U$1-PadRST)") (class "Default")
      (node (ref "U$1") (pin "RST") (pinfunction "RST_RST") (pintype "input"))
    )
    (net (code "112") (name "unconnected-(U$1-PadSUS)") (class "Default")
      (node (ref "U$1") (pin "SUS") (pinfunction "SUS_SUS") (pintype "input"))
    )
    (net (code "113") (name "unconnected-(U$1-PadTCK)") (class "Default")
      (node (ref "U$1") (pin "TCK") (pinfunction "TCK_TCK") (pintype "input"))
    )
    (net (code "114") (name "unconnected-(U$1-PadTDI)") (class "Default")
      (node (ref "U$1") (pin "TDI") (pinfunction "TDI_TDI") (pintype "input"))
    )
    (net (code "115") (name "unconnected-(U$1-PadTDO)") (class "Default")
      (node (ref "U$1") (pin "TDO") (pinfunction "TDO_TDO") (pintype "output"))
    )
    (net (code "116") (name "unconnected-(U$1-PadTMS)") (class "Default")
      (node (ref "U$1") (pin "TMS") (pinfunction "TMS_TMS") (pintype "input"))
    )
    (net (code "117") (name "unconnected-(U1-CEC_A-Pad1)") (class "Default")
      (node (ref "U1") (pin "1") (pinfunction "CEC_A_1") (pintype "bidirectional"))
    )
    (net (code "118") (name "unconnected-(U1-CEC_B-Pad7)") (class "Default")
      (node (ref "U1") (pin "7") (pinfunction "CEC_B_7") (pintype "bidirectional"))
    )
    (net (code "119") (name "unconnected-(U2-CEC_A-Pad1)") (class "Default")
      (node (ref "U2") (pin "1") (pinfunction "CEC_A_1") (pintype "bidirectional"))
    )
    (net (code "120") (name "unconnected-(U2-CEC_B-Pad7)") (class "Default")
      (node (ref "U2") (pin "7") (pinfunction "CEC_B_7") (pintype "bidirectional"))
    )
    (net (code "121") (name "unconnected-(Y1-~{CLK}-PadP$5)") (class "Default")
      (node (ref "Y1") (pin "P$5") (pinfunction "~{CLK}_P$5") (pintype "bidirectional"))
    )
  )
)
